# kiosk_power_revB.net
KiCad netlist of a schematic drawn in EAGLE
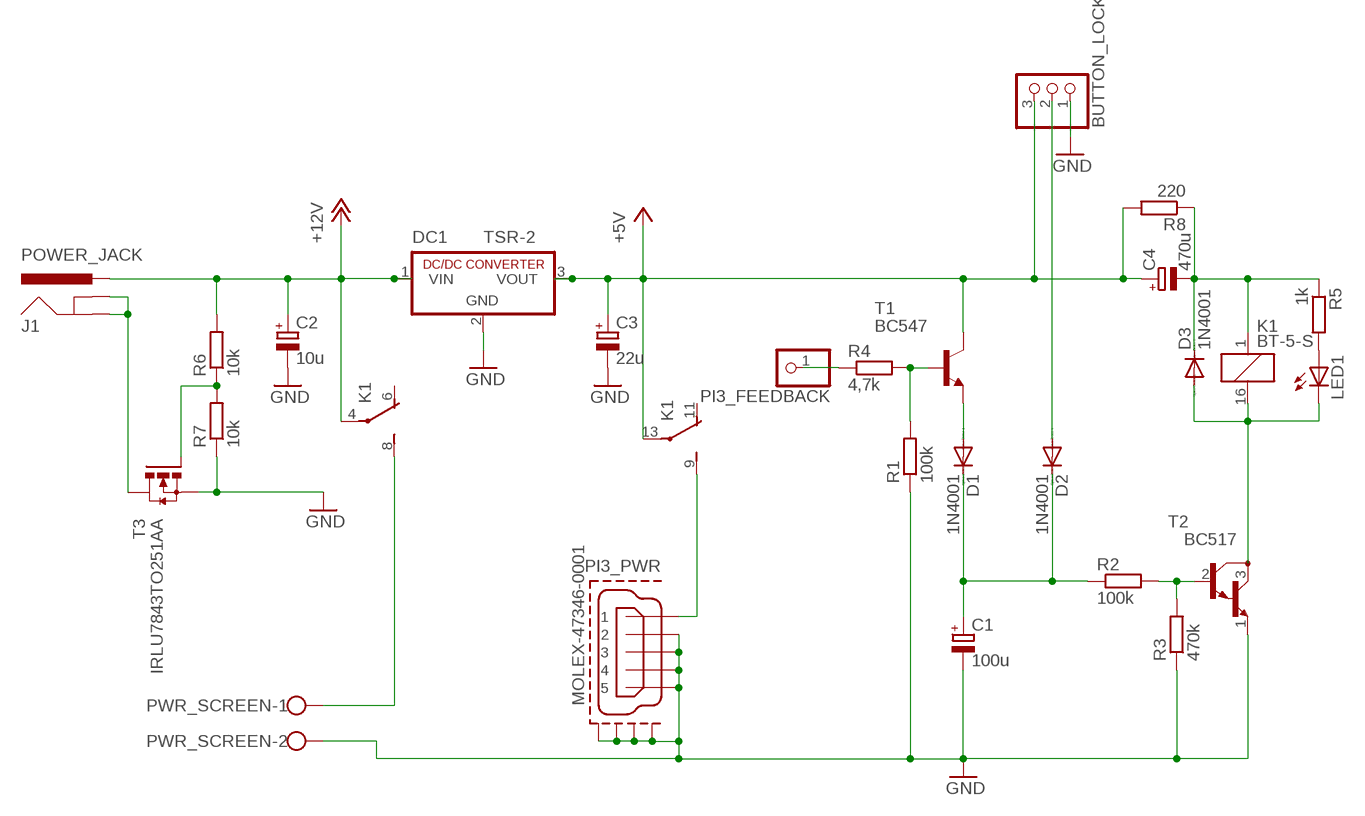
[diagram p0: schematic, sheet 1]

(export (version "E")
  (design (tool "Eeschema 10.0.6"))
  (components
    (comp (ref "BUTTON_LOCK")
      (value "PINHD-1X3/90")
      (footprint "eagle-import:1X03_90")
      (libsource (lib "eagle-import") (part "PINHD-1X3/90"))
    )
    (comp (ref "C1")
      (value "100u")
      (footprint "eagle-import:E2,5-5")
      (libsource (lib "eagle-import") (part "CPOL-EUE2.5-5"))
    )
    (comp (ref "C2")
      (value "10u")
      (footprint "eagle-import:E2,5-6")
      (libsource (lib "eagle-import") (part "CPOL-EUE2.5-6"))
    )
    (comp (ref "C3")
      (value "22u")
      (footprint "eagle-import:E2,5-5")
      (libsource (lib "eagle-import") (part "CPOL-EUE2.5-5"))
    )
    (comp (ref "C4")
      (value "470u")
      (footprint "eagle-import:E2-5")
      (libsource (lib "eagle-import") (part "CPOL-EUE2-5"))
    )
    (comp (ref "D1")
      (value "1N4001")
      (footprint "eagle-import:DO41-10")
      (libsource (lib "eagle-import") (part "1N4001"))
    )
    (comp (ref "D2")
      (value "1N4001")
      (footprint "eagle-import:DO41-10")
      (libsource (lib "eagle-import") (part "1N4001"))
    )
    (comp (ref "D3")
      (value "1N4001")
      (footprint "eagle-import:DO41-10")
      (libsource (lib "eagle-import") (part "1N4001"))
    )
    (comp (ref "DC1")
      (value "TSR-2")
      (footprint "eagle-import:SIP3")
      (fields (field (name "MF") "Traco"))
      (libsource (lib "eagle-import") (part "TSR-2"))
    )
    (comp (ref "J1")
      (value "POWER_JACK")
      (footprint "eagle-import:POWER_JACK_PTH")
      (libsource (lib "eagle-import") (part "POWER_JACK"))
    )
    (comp (ref "K1")
      (value "BT-5-S")
      (footprint "eagle-import:BT-XX-S")
      (libsource (lib "eagle-import") (part "BT--S5"))
    )
    (comp (ref "LED1")
      (value "LED3MM")
      (footprint "eagle-import:LED3MM")
      (libsource (lib "eagle-import") (part "LED3MM"))
    )
    (comp (ref "PI3_FEEDBACK")
      (value "PINHD-1X1/90")
      (footprint "eagle-import:1X01_90")
      (libsource (lib "eagle-import") (part "PINHD-1X1/90"))
    )
    (comp (ref "PI3_PWR")
      (value "MOLEX-47346-0001")
      (footprint "eagle-import:MOLEX-47364-0001")
      (libsource (lib "eagle-import") (part "MOLEX-47346-0001"))
    )
    (comp (ref "PWR_SCREEN")
      (value "W237-102")
      (footprint "eagle-import:W237-102")
      (fields (field (name "MPN") "237-102"))
      (libsource (lib "eagle-import") (part "W237-102"))
    )
    (comp (ref "R1")
      (value "100k")
      (footprint "eagle-import:0207_7")
      (libsource (lib "eagle-import") (part "R-EU_0207/7"))
    )
    (comp (ref "R2")
      (value "100k")
      (footprint "eagle-import:0207_7")
      (libsource (lib "eagle-import") (part "R-EU_0207/7"))
    )
    (comp (ref "R3")
      (value "470k")
      (footprint "eagle-import:0207_7")
      (libsource (lib "eagle-import") (part "R-EU_0207/7"))
    )
    (comp (ref "R4")
      (value "4,7k")
      (footprint "eagle-import:0207_7")
      (libsource (lib "eagle-import") (part "R-EU_0207/7"))
    )
    (comp (ref "R5")
      (value "1k")
      (footprint "eagle-import:0207_7")
      (libsource (lib "eagle-import") (part "R-EU_0207/7"))
    )
    (comp (ref "R6")
      (value "10k")
      (footprint "eagle-import:0207_7")
      (libsource (lib "eagle-import") (part "R-EU_0207/7"))
    )
    (comp (ref "R7")
      (value "10k")
      (footprint "eagle-import:0207_7")
      (libsource (lib "eagle-import") (part "R-EU_0207/7"))
    )
    (comp (ref "R8")
      (value "220")
      (footprint "eagle-import:0207_7")
      (libsource (lib "eagle-import") (part "R-EU_0207/7"))
    )
    (comp (ref "T1")
      (value "BC547")
      (footprint "eagle-import:TO92")
      (libsource (lib "eagle-import") (part "BC547"))
    )
    (comp (ref "T2")
      (value "BC517")
      (footprint "eagle-import:TO92")
      (libsource (lib "eagle-import") (part "BC517"))
    )
    (comp (ref "T3")
      (value "IRLU7843TO251AA")
      (footprint "eagle-import:TO251AA-V")
      (fields (field (name "MF") "International Rectifier"))
      (libsource (lib "eagle-import") (part "IRLU7843TO251AA"))
    )
  )
  (nets
    (net (code "1") (name "+5V") (class "Default")
      (node (ref "BUTTON_LOCK") (pin "3") (pinfunction "3_3") (pintype "passive"))
      (node (ref "C3") (pin "+") (pinfunction "+_+") (pintype "passive"))
      (node (ref "C4") (pin "+") (pinfunction "+_+") (pintype "passive"))
      (node (ref "DC1") (pin "3") (pinfunction "VOUT_3") (pintype "passive"))
      (node (ref "K1") (pin "13") (pinfunction "P_13") (pintype "passive"))
      (node (ref "R8") (pin "2") (pinfunction "2_2") (pintype "passive"))
      (node (ref "T1") (pin "3") (pinfunction "C_3") (pintype "passive"))
    )
    (net (code "2") (name "+12V") (class "Default")
      (node (ref "C2") (pin "+") (pinfunction "+_+") (pintype "passive"))
      (node (ref "DC1") (pin "1") (pinfunction "VIN_1") (pintype "passive"))
      (node (ref "J1") (pin "PWR") (pinfunction "PWR_PWR") (pintype "bidirectional"))
      (node (ref "K1") (pin "4") (pinfunction "P_4") (pintype "passive"))
      (node (ref "R6") (pin "2") (pinfunction "2_2") (pintype "passive"))
    )
    (net (code "3") (name "GND") (class "Default")
      (node (ref "BUTTON_LOCK") (pin "1") (pinfunction "1_1") (pintype "passive"))
      (node (ref "C1") (pin "-") (pinfunction "-_-") (pintype "passive"))
      (node (ref "C2") (pin "-") (pinfunction "-_-") (pintype "passive"))
      (node (ref "C3") (pin "-") (pinfunction "-_-") (pintype "passive"))
      (node (ref "DC1") (pin "2") (pinfunction "GND_2") (pintype "passive"))
      (node (ref "PI3_PWR") (pin "2") (pinfunction "2_2") (pintype "input"))
      (node (ref "PI3_PWR") (pin "3") (pinfunction "3_3") (pintype "input"))
      (node (ref "PI3_PWR") (pin "4") (pinfunction "4_4") (pintype "input"))
      (node (ref "PI3_PWR") (pin "5") (pinfunction "5_5") (pintype "input"))
      (node (ref "PI3_PWR") (pin "GND1") (pinfunction "GND1_GND1") (pintype "bidirectional"))
      (node (ref "PI3_PWR") (pin "GND2") (pinfunction "GND2_GND2") (pintype "bidirectional"))
      (node (ref "PI3_PWR") (pin "GND3") (pinfunction "GND3_GND3") (pintype "bidirectional"))
      (node (ref "PI3_PWR") (pin "GND4") (pinfunction "GND4_GND4") (pintype "bidirectional"))
      (node (ref "PWR_SCREEN") (pin "2") (pinfunction "KL_2") (pintype "passive"))
      (node (ref "R1") (pin "1") (pinfunction "1_1") (pintype "passive"))
      (node (ref "R3") (pin "1") (pinfunction "1_1") (pintype "passive"))
      (node (ref "R7") (pin "1") (pinfunction "1_1") (pintype "passive"))
      (node (ref "T2") (pin "1") (pinfunction "E_1") (pintype "passive"))
      (node (ref "T3") (pin "3") (pinfunction "S_3") (pintype "passive"))
    )
    (net (code "4") (name "Net-(BUTTON_LOCK-Pad2)") (class "Default")
      (node (ref "BUTTON_LOCK") (pin "2") (pinfunction "2_2") (pintype "passive"))
      (node (ref "D2") (pin "A") (pinfunction "A_A") (pintype "passive"))
    )
    (net (code "5") (name "Net-(C1-Pad+)") (class "Default")
      (node (ref "C1") (pin "+") (pinfunction "+_+") (pintype "passive"))
      (node (ref "D1") (pin "C") (pinfunction "C_C") (pintype "passive"))
      (node (ref "D2") (pin "C") (pinfunction "C_C") (pintype "passive"))
      (node (ref "R2") (pin "1") (pinfunction "1_1") (pintype "passive"))
    )
    (net (code "6") (name "Net-(C4-Pad-)") (class "Default")
      (node (ref "C4") (pin "-") (pinfunction "-_-") (pintype "passive"))
      (node (ref "D3") (pin "C") (pinfunction "C_C") (pintype "passive"))
      (node (ref "K1") (pin "1") (pinfunction "1_1") (pintype "passive"))
      (node (ref "R5") (pin "1") (pinfunction "1_1") (pintype "passive"))
      (node (ref "R8") (pin "1") (pinfunction "1_1") (pintype "passive"))
    )
    (net (code "7") (name "Net-(K1A-S)") (class "Default")
      (node (ref "K1") (pin "8") (pinfunction "S_8") (pintype "passive"))
      (node (ref "PWR_SCREEN") (pin "1") (pinfunction "KL_1") (pintype "passive"))
    )
    (net (code "8") (name "Net-(K1B-S)") (class "Default")
      (node (ref "K1") (pin "9") (pinfunction "S_9") (pintype "passive"))
      (node (ref "PI3_PWR") (pin "1") (pinfunction "1_1") (pintype "input"))
    )
    (net (code "9") (name "Net-(K1C-2)") (class "Default")
      (node (ref "D3") (pin "A") (pinfunction "A_A") (pintype "passive"))
      (node (ref "K1") (pin "16") (pinfunction "2_16") (pintype "passive"))
      (node (ref "LED1") (pin "K") (pinfunction "C_K") (pintype "passive"))
      (node (ref "T2") (pin "3") (pinfunction "C_3") (pintype "passive"))
    )
    (net (code "10") (name "Net-(LED1-PadA)") (class "Default")
      (node (ref "LED1") (pin "A") (pinfunction "A_A") (pintype "passive"))
      (node (ref "R5") (pin "2") (pinfunction "2_2") (pintype "passive"))
    )
    (net (code "11") (name "Net-(PI3_FEEDBACK-Pad1)") (class "Default")
      (node (ref "PI3_FEEDBACK") (pin "1") (pinfunction "1_1") (pintype "passive"))
      (node (ref "R4") (pin "1") (pinfunction "1_1") (pintype "passive"))
    )
    (net (code "12") (name "Net-(T1-B)") (class "Default")
      (node (ref "R1") (pin "2") (pinfunction "2_2") (pintype "passive"))
      (node (ref "R4") (pin "2") (pinfunction "2_2") (pintype "passive"))
      (node (ref "T1") (pin "2") (pinfunction "B_2") (pintype "passive"))
    )
    (net (code "13") (name "Net-(T1-E)") (class "Default")
      (node (ref "D1") (pin "A") (pinfunction "A_A") (pintype "passive"))
      (node (ref "T1") (pin "1") (pinfunction "E_1") (pintype "passive"))
    )
    (net (code "14") (name "Net-(T2-B)") (class "Default")
      (node (ref "R2") (pin "2") (pinfunction "2_2") (pintype "passive"))
      (node (ref "R3") (pin "2") (pinfunction "2_2") (pintype "passive"))
      (node (ref "T2") (pin "2") (pinfunction "B_2") (pintype "passive"))
    )
    (net (code "15") (name "Net-(T3-D)") (class "Default")
      (node (ref "J1") (pin "GND") (pinfunction "GND_GND") (pintype "bidirectional"))
      (node (ref "J1") (pin "GNDBREAK") (pinfunction "GNDBREAK_GNDBREAK") (pintype "bidirectional"))
      (node (ref "T3") (pin "2") (pinfunction "D_2") (pintype "passive"))
    )
    (net (code "16") (name "Net-(T3-G)") (class "Default")
      (node (ref "R6") (pin "1") (pinfunction "1_1") (pintype "passive"))
      (node (ref "R7") (pin "2") (pinfunction "2_2") (pintype "passive"))
      (node (ref "T3") (pin "1") (pinfunction "G_1") (pintype "passive"))
    )
    (net (code "17") (name "unconnected-(K1A-O-Pad6)") (class "Default")
      (node (ref "K1") (pin "6") (pinfunction "O_6") (pintype "passive"))
    )
    (net (code "18") (name "unconnected-(K1B-O-Pad11)") (class "Default")
      (node (ref "K1") (pin "11") (pinfunction "O_11") (pintype "passive"))
    )
  )
)
